# shift-register-daughter.net
KiCad netlist of a schematic drawn in EAGLE
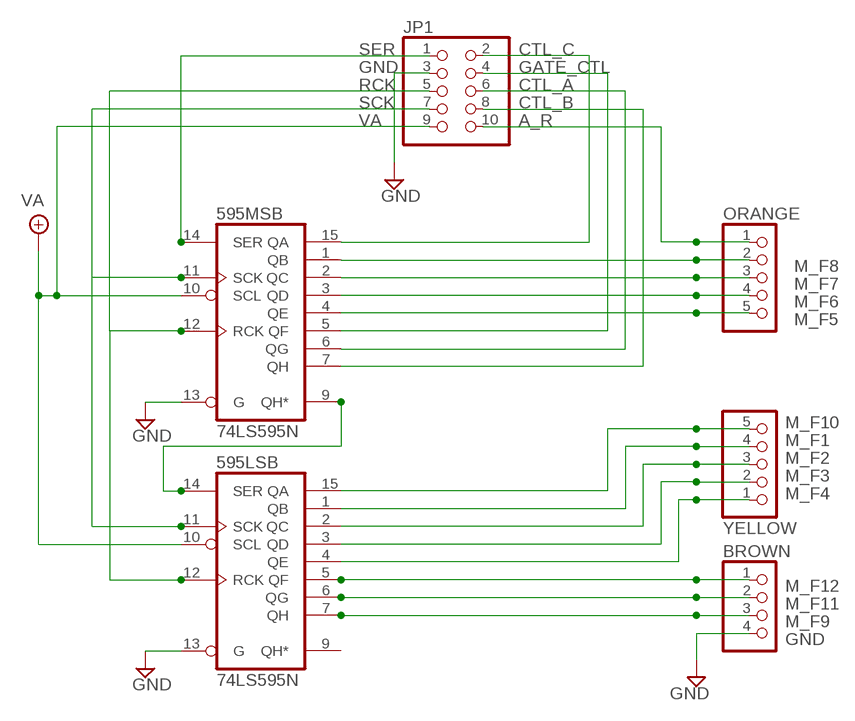
[diagram p0: schematic, sheet 1]

(export (version "E")
  (design (tool "Eeschema 10.0.6"))
  (components
    (comp (ref "595LSB")
      (value "74LS595N")
      (footprint "eagle-import:DIL16")
      (libsource (lib "eagle-import") (part "74595NLS"))
    )
    (comp (ref "595MSB")
      (value "74LS595N")
      (footprint "eagle-import:DIL16")
      (libsource (lib "eagle-import") (part "74595NLS"))
    )
    (comp (ref "BROWN")
      (value "PINHD-1X4")
      (footprint "eagle-import:1X04")
      (libsource (lib "eagle-import") (part "PINHD-1X4"))
    )
    (comp (ref "JP1")
      (value "PINHD-2X5")
      (footprint "eagle-import:2X05")
      (libsource (lib "eagle-import") (part "PINHD-2X5"))
    )
    (comp (ref "ORANGE")
      (value "PINHD-1X5")
      (footprint "eagle-import:1X05")
      (libsource (lib "eagle-import") (part "PINHD-1X5"))
    )
    (comp (ref "YELLOW")
      (value "PINHD-1X5")
      (footprint "eagle-import:1X05")
      (libsource (lib "eagle-import") (part "PINHD-1X5"))
    )
  )
  (nets
    (net (code "1") (name "/A_R") (class "Default")
      (node (ref "JP1") (pin "10") (pinfunction "10_10") (pintype "passive"))
      (node (ref "ORANGE") (pin "1") (pinfunction "1_1") (pintype "passive"))
    )
    (net (code "2") (name "/CTL_A") (class "Default")
      (node (ref "595MSB") (pin "6") (pinfunction "QG_6") (pintype "tri_state"))
      (node (ref "JP1") (pin "6") (pinfunction "6_6") (pintype "passive"))
    )
    (net (code "3") (name "/CTL_B") (class "Default")
      (node (ref "595MSB") (pin "7") (pinfunction "QH_7") (pintype "tri_state"))
      (node (ref "JP1") (pin "8") (pinfunction "8_8") (pintype "passive"))
    )
    (net (code "4") (name "/CTL_C") (class "Default")
      (node (ref "595MSB") (pin "15") (pinfunction "QA_15") (pintype "tri_state"))
      (node (ref "JP1") (pin "2") (pinfunction "2_2") (pintype "passive"))
    )
    (net (code "5") (name "/GATE_CTL") (class "Default")
      (node (ref "595MSB") (pin "5") (pinfunction "QF_5") (pintype "tri_state"))
      (node (ref "JP1") (pin "4") (pinfunction "4_4") (pintype "passive"))
    )
    (net (code "6") (name "/M_F1") (class "Default")
      (node (ref "595LSB") (pin "1") (pinfunction "QB_1") (pintype "tri_state"))
      (node (ref "YELLOW") (pin "4") (pinfunction "4_4") (pintype "passive"))
    )
    (net (code "7") (name "/M_F2") (class "Default")
      (node (ref "595LSB") (pin "2") (pinfunction "QC_2") (pintype "tri_state"))
      (node (ref "YELLOW") (pin "3") (pinfunction "3_3") (pintype "passive"))
    )
    (net (code "8") (name "/M_F3") (class "Default")
      (node (ref "595LSB") (pin "3") (pinfunction "QD_3") (pintype "tri_state"))
      (node (ref "YELLOW") (pin "2") (pinfunction "2_2") (pintype "passive"))
    )
    (net (code "9") (name "/M_F4") (class "Default")
      (node (ref "595LSB") (pin "4") (pinfunction "QE_4") (pintype "tri_state"))
      (node (ref "YELLOW") (pin "1") (pinfunction "1_1") (pintype "passive"))
    )
    (net (code "10") (name "/M_F5") (class "Default")
      (node (ref "595MSB") (pin "4") (pinfunction "QE_4") (pintype "tri_state"))
      (node (ref "ORANGE") (pin "5") (pinfunction "5_5") (pintype "passive"))
    )
    (net (code "11") (name "/M_F6") (class "Default")
      (node (ref "595MSB") (pin "3") (pinfunction "QD_3") (pintype "tri_state"))
      (node (ref "ORANGE") (pin "4") (pinfunction "4_4") (pintype "passive"))
    )
    (net (code "12") (name "/M_F7") (class "Default")
      (node (ref "595MSB") (pin "2") (pinfunction "QC_2") (pintype "tri_state"))
      (node (ref "ORANGE") (pin "3") (pinfunction "3_3") (pintype "passive"))
    )
    (net (code "13") (name "/M_F8") (class "Default")
      (node (ref "595MSB") (pin "1") (pinfunction "QB_1") (pintype "tri_state"))
      (node (ref "ORANGE") (pin "2") (pinfunction "2_2") (pintype "passive"))
    )
    (net (code "14") (name "/M_F9") (class "Default")
      (node (ref "595LSB") (pin "7") (pinfunction "QH_7") (pintype "tri_state"))
      (node (ref "BROWN") (pin "3") (pinfunction "3_3") (pintype "passive"))
    )
    (net (code "15") (name "/M_F10") (class "Default")
      (node (ref "595LSB") (pin "15") (pinfunction "QA_15") (pintype "tri_state"))
      (node (ref "YELLOW") (pin "5") (pinfunction "5_5") (pintype "passive"))
    )
    (net (code "16") (name "/M_F11") (class "Default")
      (node (ref "595LSB") (pin "6") (pinfunction "QG_6") (pintype "tri_state"))
      (node (ref "BROWN") (pin "2") (pinfunction "2_2") (pintype "passive"))
    )
    (net (code "17") (name "/M_F12") (class "Default")
      (node (ref "595LSB") (pin "5") (pinfunction "QF_5") (pintype "tri_state"))
      (node (ref "BROWN") (pin "1") (pinfunction "1_1") (pintype "passive"))
    )
    (net (code "18") (name "/RCK") (class "Default")
      (node (ref "595LSB") (pin "12") (pinfunction "RCK_12") (pintype "input"))
      (node (ref "595MSB") (pin "12") (pinfunction "RCK_12") (pintype "input"))
      (node (ref "JP1") (pin "5") (pinfunction "5_5") (pintype "passive"))
    )
    (net (code "19") (name "/SCK") (class "Default")
      (node (ref "595LSB") (pin "11") (pinfunction "SCK_11") (pintype "input"))
      (node (ref "595MSB") (pin "11") (pinfunction "SCK_11") (pintype "input"))
      (node (ref "JP1") (pin "7") (pinfunction "7_7") (pintype "passive"))
    )
    (net (code "20") (name "/SER") (class "Default")
      (node (ref "595MSB") (pin "14") (pinfunction "SER_14") (pintype "input"))
      (node (ref "JP1") (pin "1") (pinfunction "1_1") (pintype "passive"))
    )
    (net (code "21") (name "GND") (class "Default")
      (node (ref "595LSB") (pin "13") (pinfunction "G_13") (pintype "input"))
      (node (ref "595MSB") (pin "13") (pinfunction "G_13") (pintype "input"))
      (node (ref "BROWN") (pin "4") (pinfunction "4_4") (pintype "passive"))
      (node (ref "JP1") (pin "3") (pinfunction "3_3") (pintype "passive"))
    )
    (net (code "22") (name "Net-(595LSBA-SER)") (class "Default")
      (node (ref "595LSB") (pin "14") (pinfunction "SER_14") (pintype "input"))
      (node (ref "595MSB") (pin "9") (pinfunction "QH*_9") (pintype "tri_state"))
    )
    (net (code "23") (name "VA") (class "Default")
      (node (ref "595LSB") (pin "10") (pinfunction "SCL_10") (pintype "input"))
      (node (ref "595MSB") (pin "10") (pinfunction "SCL_10") (pintype "input"))
      (node (ref "JP1") (pin "9") (pinfunction "9_9") (pintype "passive"))
    )
    (net (code "24") (name "unconnected-(595LSBA-QH*-Pad9)") (class "Default")
      (node (ref "595LSB") (pin "9") (pinfunction "QH*_9") (pintype "tri_state"))
    )
  )
)
